# WiFi_Module.net
KiCad netlist of a schematic drawn in EAGLE
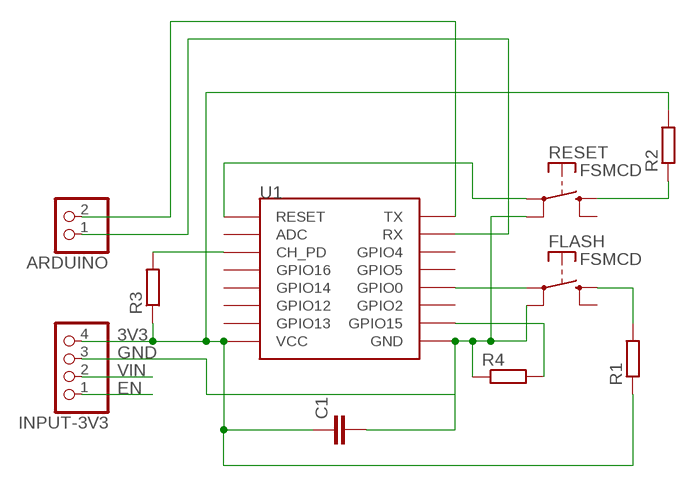
[diagram p0: schematic, sheet 1]

(export (version "E")
  (design (tool "Eeschema 10.0.6"))
  (components
    (comp (ref "ARDUINO")
      (value "PINHD-1X2")
      (footprint "eagle-import:1X02")
      (libsource (lib "eagle-import") (part "PINHD-1X2"))
    )
    (comp (ref "C1")
      (value "C2.5/2")
      (footprint "eagle-import:C2.5-2")
      (libsource (lib "eagle-import") (part "C2.5/2"))
    )
    (comp (ref "FLASH")
      (value "FSMCD")
      (footprint "eagle-import:FSMCD")
      (libsource (lib "eagle-import") (part "FSMCD"))
    )
    (comp (ref "INPUT-3V3")
      (value "PINHD-1X4")
      (footprint "eagle-import:1X04")
      (libsource (lib "eagle-import") (part "PINHD-1X4"))
    )
    (comp (ref "R1")
      (value "R-EU_0204/5")
      (footprint "eagle-import:0204_5")
      (libsource (lib "eagle-import") (part "R-EU_0204/5"))
    )
    (comp (ref "R2")
      (value "R-EU_0204/5")
      (footprint "eagle-import:0204_5")
      (libsource (lib "eagle-import") (part "R-EU_0204/5"))
    )
    (comp (ref "R3")
      (value "R-EU_0204/5")
      (footprint "eagle-import:0204_5")
      (libsource (lib "eagle-import") (part "R-EU_0204/5"))
    )
    (comp (ref "R4")
      (value "R-EU_0204/5")
      (footprint "eagle-import:0204_5")
      (libsource (lib "eagle-import") (part "R-EU_0204/5"))
    )
    (comp (ref "RESET")
      (value "FSMCD")
      (footprint "eagle-import:FSMCD")
      (libsource (lib "eagle-import") (part "FSMCD"))
    )
    (comp (ref "U1")
      (value "ESP12SMD")
      (footprint "eagle-import:ESP12-SMD")
      (libsource (lib "eagle-import") (part "ESP12SMD"))
    )
  )
  (nets
    (net (code "1") (name "/3V3") (class "Default")
      (node (ref "C1") (pin "1") (pinfunction "1_1") (pintype "passive"))
      (node (ref "INPUT-3V3") (pin "4") (pinfunction "4_4") (pintype "passive"))
      (node (ref "R1") (pin "1") (pinfunction "1_1") (pintype "passive"))
      (node (ref "R2") (pin "2") (pinfunction "2_2") (pintype "passive"))
      (node (ref "R3") (pin "1") (pinfunction "1_1") (pintype "passive"))
      (node (ref "U1") (pin "VCC") (pinfunction "VCC_VCC") (pintype "bidirectional"))
    )
    (net (code "2") (name "/EN") (class "Default")
      (node (ref "INPUT-3V3") (pin "1") (pinfunction "1_1") (pintype "passive"))
    )
    (net (code "3") (name "/GND") (class "Default")
      (node (ref "C1") (pin "2") (pinfunction "2_2") (pintype "passive"))
      (node (ref "FLASH") (pin "P$2") (pinfunction "P_P$2") (pintype "passive"))
      (node (ref "INPUT-3V3") (pin "3") (pinfunction "3_3") (pintype "passive"))
      (node (ref "R4") (pin "1") (pinfunction "1_1") (pintype "passive"))
      (node (ref "RESET") (pin "P$2") (pinfunction "P_P$2") (pintype "passive"))
      (node (ref "U1") (pin "GND") (pinfunction "GND_GND") (pintype "bidirectional"))
    )
    (net (code "4") (name "/VIN") (class "Default")
      (node (ref "INPUT-3V3") (pin "2") (pinfunction "2_2") (pintype "passive"))
    )
    (net (code "5") (name "Net-(FLASH-P-PadP$1)") (class "Default")
      (node (ref "FLASH") (pin "P$1") (pinfunction "P_P$1") (pintype "passive"))
      (node (ref "U1") (pin "GPIO0") (pinfunction "GPIO0_GPIO0") (pintype "bidirectional"))
    )
    (net (code "6") (name "Net-(FLASH-S-PadP$3)") (class "Default")
      (node (ref "FLASH") (pin "P$3") (pinfunction "S_P$3") (pintype "passive"))
      (node (ref "R1") (pin "2") (pinfunction "2_2") (pintype "passive"))
    )
    (net (code "7") (name "Net-(R2-Pad1)") (class "Default")
      (node (ref "R2") (pin "1") (pinfunction "1_1") (pintype "passive"))
      (node (ref "RESET") (pin "P$3") (pinfunction "S_P$3") (pintype "passive"))
    )
    (net (code "8") (name "Net-(R3-Pad2)") (class "Default")
      (node (ref "R3") (pin "2") (pinfunction "2_2") (pintype "passive"))
      (node (ref "U1") (pin "CH_PD") (pinfunction "CH_PD_CH_PD") (pintype "bidirectional"))
    )
    (net (code "9") (name "Net-(R4-Pad2)") (class "Default")
      (node (ref "R4") (pin "2") (pinfunction "2_2") (pintype "passive"))
      (node (ref "U1") (pin "GPIO15") (pinfunction "GPIO15_GPIO15") (pintype "bidirectional"))
    )
    (net (code "10") (name "Net-(RESET-P-PadP$1)") (class "Default")
      (node (ref "RESET") (pin "P$1") (pinfunction "P_P$1") (pintype "passive"))
      (node (ref "U1") (pin "RESET") (pinfunction "RESET_RESET") (pintype "bidirectional"))
    )
    (net (code "11") (name "Net-(U1-RX)") (class "Default")
      (node (ref "ARDUINO") (pin "1") (pinfunction "1_1") (pintype "passive"))
      (node (ref "U1") (pin "RXD0") (pinfunction "RX_RXD0") (pintype "bidirectional"))
    )
    (net (code "12") (name "Net-(U1-TX)") (class "Default")
      (node (ref "ARDUINO") (pin "2") (pinfunction "2_2") (pintype "passive"))
      (node (ref "U1") (pin "TXD0") (pinfunction "TX_TXD0") (pintype "bidirectional"))
    )
    (net (code "13") (name "unconnected-(FLASH-S-PadP$4)") (class "Default")
      (node (ref "FLASH") (pin "P$4") (pinfunction "S_P$4") (pintype "passive"))
    )
    (net (code "14") (name "unconnected-(RESET-S-PadP$4)") (class "Default")
      (node (ref "RESET") (pin "P$4") (pinfunction "S_P$4") (pintype "passive"))
    )
    (net (code "15") (name "unconnected-(U1-PadADC)") (class "Default")
      (node (ref "U1") (pin "ADC") (pinfunction "ADC_ADC") (pintype "bidirectional"))
    )
    (net (code "16") (name "unconnected-(U1-PadGPIO2)") (class "Default")
      (node (ref "U1") (pin "GPIO2") (pinfunction "GPIO2_GPIO2") (pintype "bidirectional"))
    )
    (net (code "17") (name "unconnected-(U1-PadGPIO4)") (class "Default")
      (node (ref "U1") (pin "GPIO4") (pinfunction "GPIO4_GPIO4") (pintype "bidirectional"))
    )
    (net (code "18") (name "unconnected-(U1-PadGPIO5)") (class "Default")
      (node (ref "U1") (pin "GPIO5") (pinfunction "GPIO5_GPIO5") (pintype "bidirectional"))
    )
    (net (code "19") (name "unconnected-(U1-PadGPIO12)") (class "Default")
      (node (ref "U1") (pin "GPIO12") (pinfunction "GPIO12_GPIO12") (pintype "bidirectional"))
    )
    (net (code "20") (name "unconnected-(U1-PadGPIO13)") (class "Default")
      (node (ref "U1") (pin "GPIO13") (pinfunction "GPIO13_GPIO13") (pintype "bidirectional"))
    )
    (net (code "21") (name "unconnected-(U1-PadGPIO14)") (class "Default")
      (node (ref "U1") (pin "GPIO14") (pinfunction "GPIO14_GPIO14") (pintype "bidirectional"))
    )
    (net (code "22") (name "unconnected-(U1-PadGPIO16)") (class "Default")
      (node (ref "U1") (pin "GPIO16") (pinfunction "GPIO16_GPIO16") (pintype "bidirectional"))
    )
  )
)
